# Design_Project.net
KiCad netlist of a schematic drawn in EasyEDA
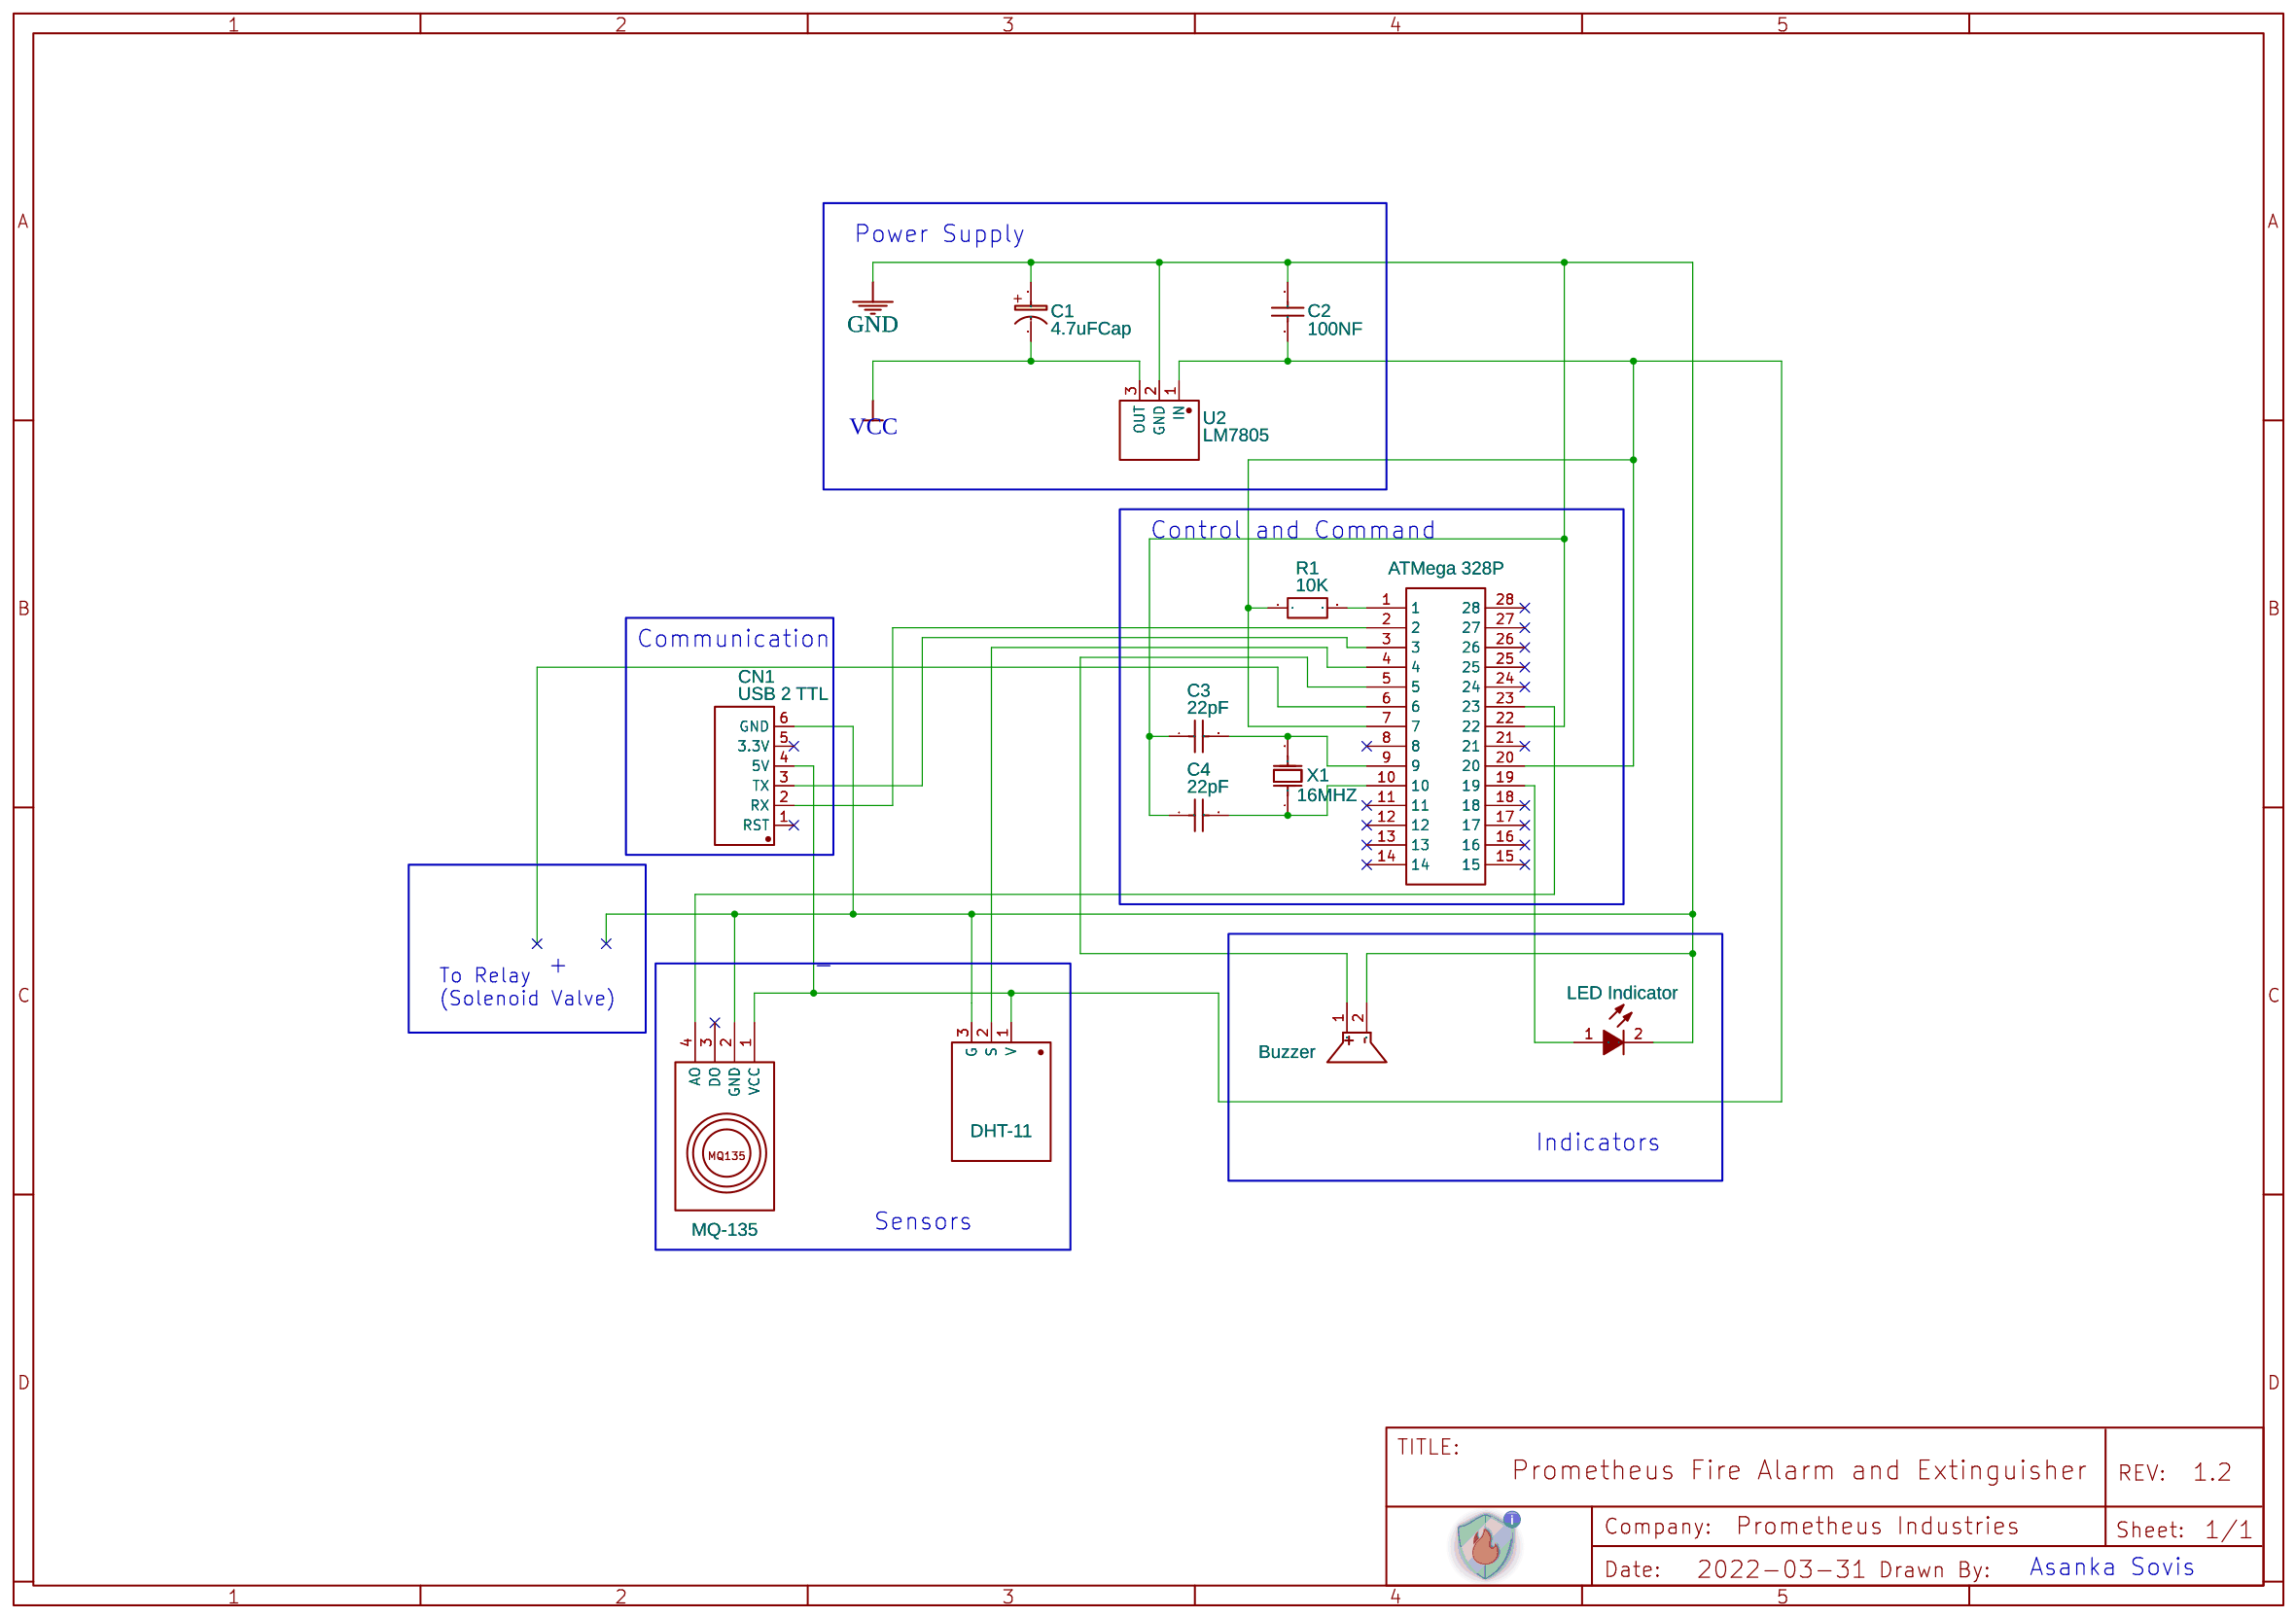
[diagram p0: schematic sheet]

(export (version "E")
  (design (tool "Eeschema 10.0.6"))
  (components
    (comp (ref "BUZZER1")
      (value "Buzzer")
      (fields
        (field (name "BOM_Manufacturer Part") "FMQ-BUZZER2")
        (field (name "BOM_Supplier Part") "C9900006103")
      )
      (libsource (lib "") (part "FMQ-BUZZER2"))
    )
    (comp (ref "C1") (value "4.7uFCap") (libsource (lib "") (part "4.7uFCap")))
    (comp (ref "C2")
      (value "100NF")
      (fields
        (field (name "BOM_Manufacturer Part") "100nF (104) ±20% 100V")
        (field (name "BOM_Supplier Part") "C72322")
      )
      (libsource (lib "") (part "100NF"))
    )
    (comp (ref "C3") (value "22pF") (libsource (lib "") (part "22pF")))
    (comp (ref "C4") (value "22pF") (libsource (lib "") (part "22pF")))
    (comp (ref "CN1")
      (value "USB 2 TTL")
      (fields
        (field (name "BOM_Manufacturer Part") "425Connectors- -07P-2.5mmWhite Grey")
        (field (name "BOM_Supplier Part") "C89538")
      )
      (libsource (lib "") (part "USB2TTL3V"))
    )
    (comp (ref "D1")
      (value "LED Indicator")
      (fields (field (name "BOM_Manufacturer Part") "5600") (field (name "BOM_Supplier Part") "L20325-ND"))
      (libsource (lib "") (part "3mm Green TH LED 5600"))
    )
    (comp (ref "R1")
      (value "10K")
      (fields
        (field (name "BOM_Manufacturer Part") "RN1/2WS10KΩFT/BA1")
        (field (name "BOM_Supplier Part") "C385441")
      )
      (libsource (lib "") (part "10k"))
    )
    (comp (ref "U1") (value "ATMega 328P") (libsource (lib "") (part "ATMega328P")))
    (comp (ref "U2")
      (value "LM7805")
      (fields (field (name "BOM_Supplier Part") "C845394"))
      (libsource (lib "") (part "LM7805"))
    )
    (comp (ref "U3") (value "MQ-135") (libsource (lib "") (part "MQ135_Sensor")))
    (comp (ref "U5")
      (value "DHT-11")
      (fields (field (name "BOM_Manufacturer Part") "DHT11") (field (name "BOM_Supplier Part") "C117051"))
      (libsource (lib "") (part "DIP-DHT11"))
    )
    (comp (ref "X1")
      (value "16MHZ")
      (fields
        (field (name "BOM_Manufacturer Part") "49SAC16000202060")
        (field (name "BOM_Supplier Part") "C390745")
      )
      (libsource (lib "") (part "CRYSTAL 16MHZ"))
    )
  )
  (nets
    (net (code "1") (name "GND") (class "Default")
      (node (ref "BUZZER1") (pin "2") (pinfunction "2_2") (pintype "unspecified"))
      (node (ref "C1") (pin "P") (pinfunction "P_P") (pintype "unspecified"))
      (node (ref "C2") (pin "2") (pinfunction "2_2") (pintype "input"))
      (node (ref "C3") (pin "1") (pinfunction "1_1") (pintype "input"))
      (node (ref "C4") (pin "1") (pinfunction "1_1") (pintype "input"))
      (node (ref "CN1") (pin "6") (pinfunction "GND_6") (pintype "unspecified"))
      (node (ref "D1") (pin "2") (pinfunction "K_2") (pintype "input"))
      (node (ref "U1") (pin "22") (pinfunction "22_22") (pintype "unspecified"))
      (node (ref "U2") (pin "2") (pinfunction "GND_2") (pintype "unspecified"))
      (node (ref "U3") (pin "2") (pinfunction "GND_2") (pintype "unspecified"))
      (node (ref "U5") (pin "3") (pinfunction "G_3") (pintype "unspecified"))
    )
    (net (code "2") (name "Net-(BUZZER1-Pad1)") (class "Default")
      (node (ref "BUZZER1") (pin "1") (pinfunction "1_1") (pintype "unspecified"))
      (node (ref "U1") (pin "5") (pinfunction "5_5") (pintype "unspecified"))
    )
    (net (code "3") (name "Net-(CN1-5V)") (class "Default")
      (node (ref "C2") (pin "1") (pinfunction "1_1") (pintype "input"))
      (node (ref "CN1") (pin "4") (pinfunction "5V_4") (pintype "unspecified"))
      (node (ref "R1") (pin "1") (pinfunction "1_1") (pintype "unspecified"))
      (node (ref "U1") (pin "20") (pinfunction "20_20") (pintype "unspecified"))
      (node (ref "U1") (pin "7") (pinfunction "7_7") (pintype "unspecified"))
      (node (ref "U2") (pin "1") (pinfunction "IN_1") (pintype "unspecified"))
      (node (ref "U3") (pin "1") (pinfunction "VCC_1") (pintype "unspecified"))
      (node (ref "U5") (pin "1") (pinfunction "V_1") (pintype "unspecified"))
    )
    (net (code "4") (name "Net-(CN1-RX)") (class "Default")
      (node (ref "CN1") (pin "2") (pinfunction "RX_2") (pintype "unspecified"))
      (node (ref "U1") (pin "2") (pinfunction "2_2") (pintype "unspecified"))
    )
    (net (code "5") (name "Net-(CN1-TX)") (class "Default")
      (node (ref "CN1") (pin "3") (pinfunction "TX_3") (pintype "unspecified"))
      (node (ref "U1") (pin "3") (pinfunction "3_3") (pintype "unspecified"))
    )
    (net (code "6") (name "Net-(D1-A)") (class "Default")
      (node (ref "D1") (pin "1") (pinfunction "A_1") (pintype "input"))
      (node (ref "U1") (pin "19") (pinfunction "19_19") (pintype "unspecified"))
    )
    (net (code "7") (name "Net-(R1-Pad2)") (class "Default")
      (node (ref "R1") (pin "2") (pinfunction "2_2") (pintype "unspecified"))
      (node (ref "U1") (pin "1") (pinfunction "1_1") (pintype "unspecified"))
    )
    (net (code "8") (name "Net-(U3-AO)") (class "Default")
      (node (ref "U1") (pin "23") (pinfunction "23_23") (pintype "unspecified"))
      (node (ref "U3") (pin "4") (pinfunction "AO_4") (pintype "unspecified"))
    )
    (net (code "9") (name "Net-(U5-S)") (class "Default")
      (node (ref "U1") (pin "4") (pinfunction "4_4") (pintype "unspecified"))
      (node (ref "U5") (pin "2") (pinfunction "S_2") (pintype "unspecified"))
    )
    (net (code "10") (name "Net-(X1-OSC1)") (class "Default")
      (node (ref "C4") (pin "2") (pinfunction "2_2") (pintype "input"))
      (node (ref "U1") (pin "10") (pinfunction "10_10") (pintype "unspecified"))
      (node (ref "X1") (pin "1") (pinfunction "OSC1_1") (pintype "input"))
    )
    (net (code "11") (name "Net-(X1-OSC2)") (class "Default")
      (node (ref "C3") (pin "2") (pinfunction "2_2") (pintype "input"))
      (node (ref "U1") (pin "9") (pinfunction "9_9") (pintype "unspecified"))
      (node (ref "X1") (pin "2") (pinfunction "OSC2_2") (pintype "input"))
    )
    (net (code "12") (name "VCC") (class "Default")
      (node (ref "C1") (pin "N") (pinfunction "N_N") (pintype "unspecified"))
      (node (ref "U2") (pin "3") (pinfunction "OUT_3") (pintype "unspecified"))
    )
    (net (code "13") (name "unconnected-(CN1-3.3V-Pad5)") (class "Default")
      (node (ref "CN1") (pin "5") (pinfunction "3.3V_5") (pintype "unspecified+no_connect"))
    )
    (net (code "14") (name "unconnected-(CN1-RST-Pad1)") (class "Default")
      (node (ref "CN1") (pin "1") (pinfunction "RST_1") (pintype "unspecified+no_connect"))
    )
    (net (code "15") (name "unconnected-(U1-Pad6)") (class "Default")
      (node (ref "U1") (pin "6") (pinfunction "6_6") (pintype "unspecified+no_connect"))
    )
    (net (code "16") (name "unconnected-(U1-Pad8)") (class "Default")
      (node (ref "U1") (pin "8") (pinfunction "8_8") (pintype "unspecified+no_connect"))
    )
    (net (code "17") (name "unconnected-(U1-Pad11)") (class "Default")
      (node (ref "U1") (pin "11") (pinfunction "11_11") (pintype "unspecified+no_connect"))
    )
    (net (code "18") (name "unconnected-(U1-Pad12)") (class "Default")
      (node (ref "U1") (pin "12") (pinfunction "12_12") (pintype "unspecified+no_connect"))
    )
    (net (code "19") (name "unconnected-(U1-Pad13)") (class "Default")
      (node (ref "U1") (pin "13") (pinfunction "13_13") (pintype "unspecified+no_connect"))
    )
    (net (code "20") (name "unconnected-(U1-Pad14)") (class "Default")
      (node (ref "U1") (pin "14") (pinfunction "14_14") (pintype "unspecified+no_connect"))
    )
    (net (code "21") (name "unconnected-(U1-Pad15)") (class "Default")
      (node (ref "U1") (pin "15") (pinfunction "15_15") (pintype "unspecified+no_connect"))
    )
    (net (code "22") (name "unconnected-(U1-Pad16)") (class "Default")
      (node (ref "U1") (pin "16") (pinfunction "16_16") (pintype "unspecified+no_connect"))
    )
    (net (code "23") (name "unconnected-(U1-Pad17)") (class "Default")
      (node (ref "U1") (pin "17") (pinfunction "17_17") (pintype "unspecified+no_connect"))
    )
    (net (code "24") (name "unconnected-(U1-Pad18)") (class "Default")
      (node (ref "U1") (pin "18") (pinfunction "18_18") (pintype "unspecified+no_connect"))
    )
    (net (code "25") (name "unconnected-(U1-Pad21)") (class "Default")
      (node (ref "U1") (pin "21") (pinfunction "21_21") (pintype "unspecified+no_connect"))
    )
    (net (code "26") (name "unconnected-(U1-Pad24)") (class "Default")
      (node (ref "U1") (pin "24") (pinfunction "24_24") (pintype "unspecified+no_connect"))
    )
    (net (code "27") (name "unconnected-(U1-Pad25)") (class "Default")
      (node (ref "U1") (pin "25") (pinfunction "25_25") (pintype "unspecified+no_connect"))
    )
    (net (code "28") (name "unconnected-(U1-Pad26)") (class "Default")
      (node (ref "U1") (pin "26") (pinfunction "26_26") (pintype "unspecified+no_connect"))
    )
    (net (code "29") (name "unconnected-(U1-Pad27)") (class "Default")
      (node (ref "U1") (pin "27") (pinfunction "27_27") (pintype "unspecified+no_connect"))
    )
    (net (code "30") (name "unconnected-(U1-Pad28)") (class "Default")
      (node (ref "U1") (pin "28") (pinfunction "28_28") (pintype "unspecified+no_connect"))
    )
    (net (code "31") (name "unconnected-(U3-DO-Pad3)") (class "Default")
      (node (ref "U3") (pin "3") (pinfunction "DO_3") (pintype "unspecified+no_connect"))
    )
  )
)
